# eeZee_medium_tiny.net
KiCad netlist of a schematic drawn in EAGLE
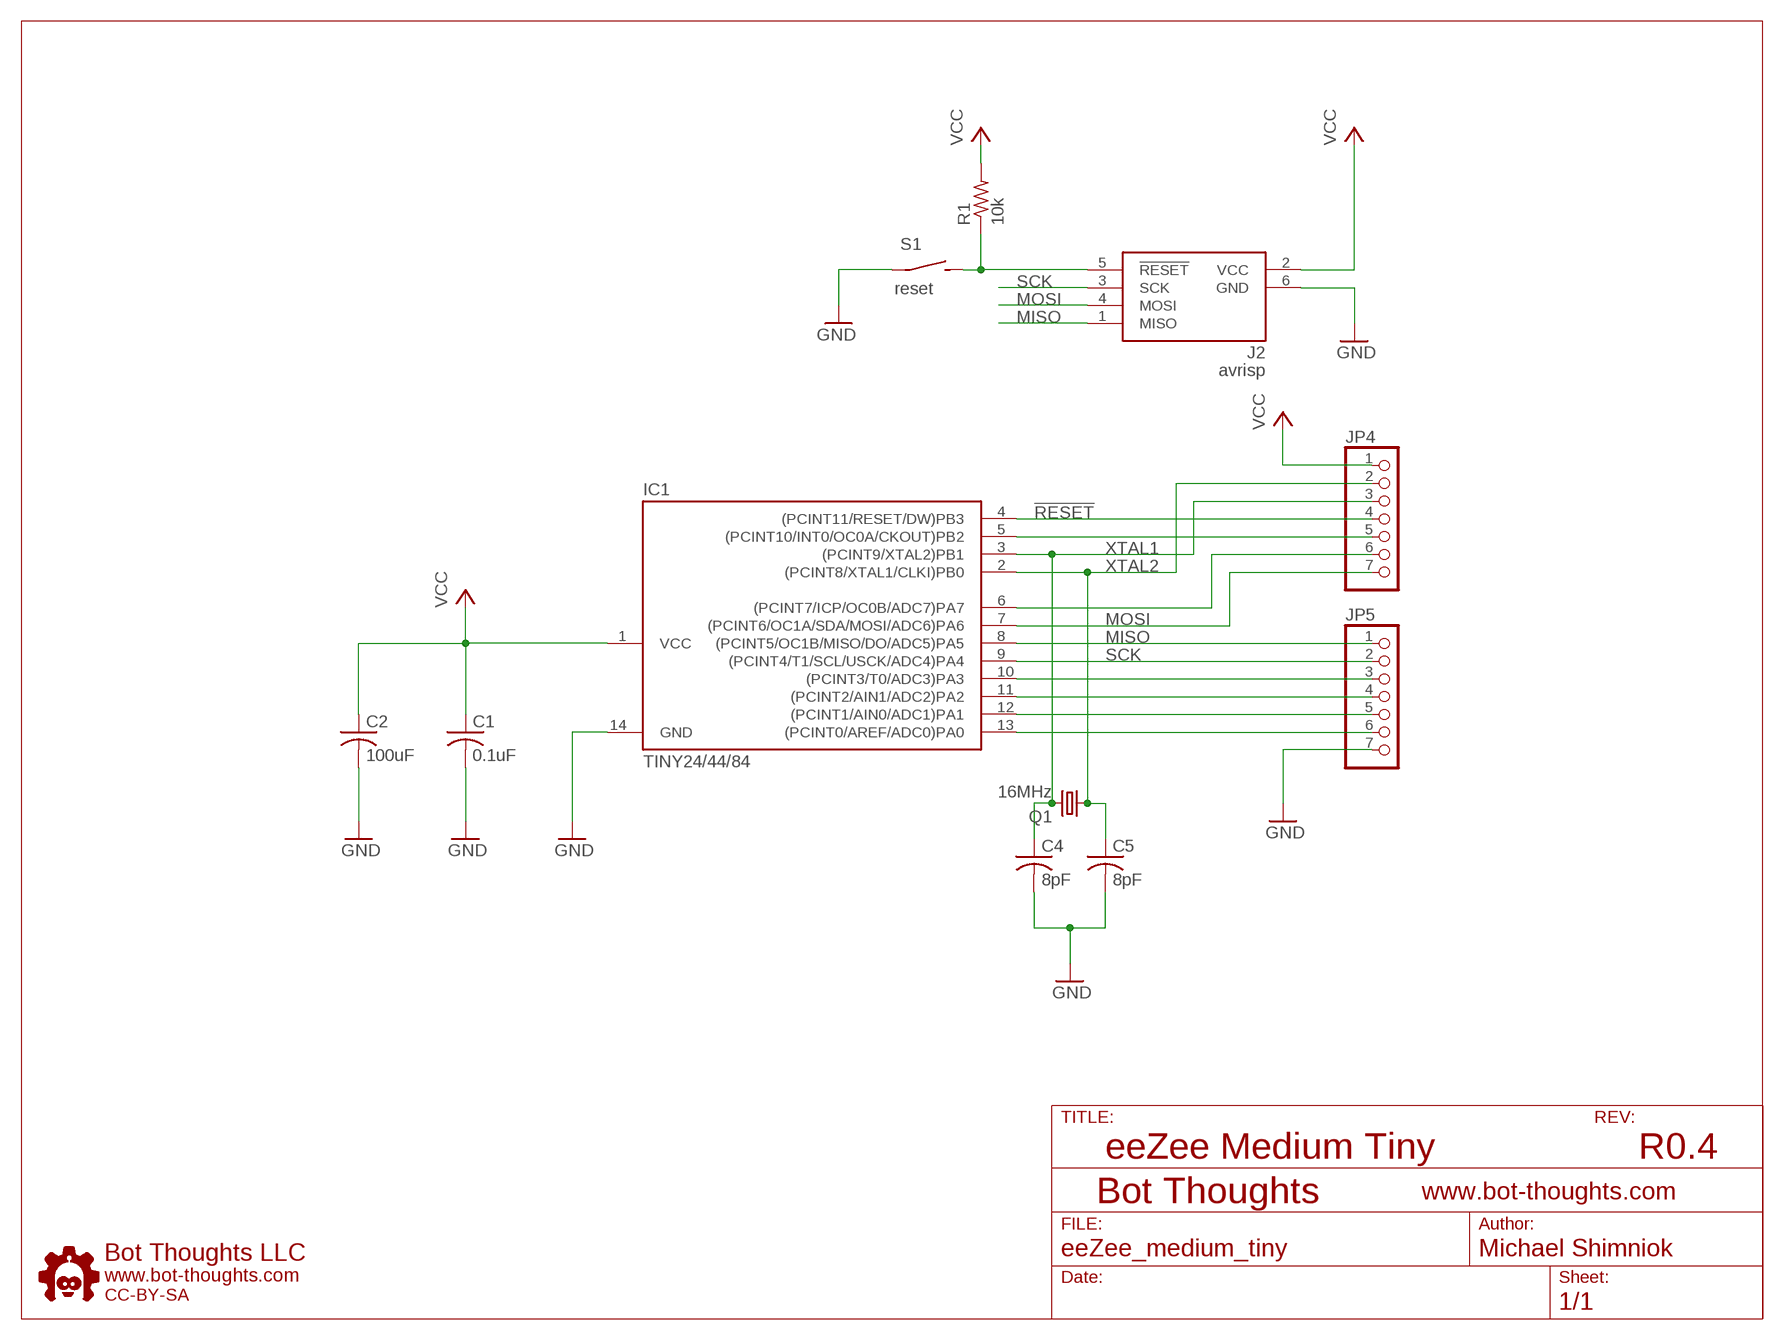
[diagram p0: schematic, sheet 1]

(export (version "E")
  (design (tool "Eeschema 10.0.6"))
  (components
    (comp (ref "C1")
      (value "0.1uF")
      (footprint "eagle-import:C0603")
      (fields (field (name "PARTNO") "0603YC104KAT2A"))
      (libsource (lib "eagle-import") (part "C-USC0603"))
    )
    (comp (ref "C2")
      (value "100uF")
      (footprint "eagle-import:C1206")
      (fields (field (name "PARTNO") "MCTT21X106M6R3CT"))
      (libsource (lib "eagle-import") (part "C-USC1206"))
    )
    (comp (ref "C4")
      (value "8pF")
      (footprint "eagle-import:C0603")
      (fields (field (name "PARTNO") "0603YC104KAT2A"))
      (libsource (lib "eagle-import") (part "C-USC0603"))
    )
    (comp (ref "C5")
      (value "8pF")
      (footprint "eagle-import:C0603")
      (fields (field (name "PARTNO") "0603YC104KAT2A"))
      (libsource (lib "eagle-import") (part "C-USC0603"))
    )
    (comp (ref "IC1")
      (value "TINY24/44/84")
      (footprint "eagle-import:DIL14")
      (libsource (lib "eagle-import") (part "TINY24/44/84-PU"))
    )
    (comp (ref "J2")
      (value "avrisp")
      (footprint "eagle-import:CON6P2R")
      (libsource (lib "eagle-import") (part "AVRISP6"))
    )
    (comp (ref "JP4")
      (value "PINHD-1X07_2.54-S")
      (footprint "eagle-import:1X07-S")
      (libsource (lib "eagle-import") (part "PINHD-1X07_2.54-S"))
    )
    (comp (ref "JP5")
      (value "PINHD-1X07_2.54-S")
      (footprint "eagle-import:1X07-S")
      (libsource (lib "eagle-import") (part "PINHD-1X07_2.54-S"))
    )
    (comp (ref "Q1")
      (value "16MHz")
      (footprint "eagle-import:NDK_2PAD_5X3")
      (libsource (lib "eagle-import") (part "CRYSTALNDK5X3"))
    )
    (comp (ref "R1")
      (value "10k")
      (footprint "eagle-import:R0603")
      (fields (field (name "PARTNO") "ERJ-3GEYJ103V"))
      (libsource (lib "eagle-import") (part "R-US_R0603"))
    )
    (comp (ref "S1")
      (value "reset")
      (footprint "eagle-import:6MMTACTILE_RECT")
      (libsource (lib "eagle-import") (part "SPST_TAC_RECT1"))
    )
    (comp (ref "U$1")
      (value "BTLOGO-LOGO-SM")
      (footprint "eagle-import:BTLOGOS")
      (libsource (lib "eagle-import") (part "BTLOGO-LOGO-SM"))
    )
  )
  (nets
    (net (code "1") (name "/MISO") (class "Default")
      (node (ref "IC1") (pin "8") (pinfunction "(PCINT5/OC1B/MISO/DO/ADC5)PA5_8") (pintype "bidirectional"))
      (node (ref "J2") (pin "1") (pinfunction "MISO_1") (pintype "input"))
      (node (ref "JP5") (pin "1") (pinfunction "1_1") (pintype "passive"))
    )
    (net (code "2") (name "/MOSI") (class "Default")
      (node (ref "IC1") (pin "7") (pinfunction "(PCINT6/OC1A/SDA/MOSI/ADC6)PA6_7") (pintype "bidirectional"))
      (node (ref "J2") (pin "4") (pinfunction "MOSI_4") (pintype "output"))
      (node (ref "JP4") (pin "7") (pinfunction "7_7") (pintype "passive"))
    )
    (net (code "3") (name "/SCK") (class "Default")
      (node (ref "IC1") (pin "9") (pinfunction "(PCINT4/T1/SCL/USCK/ADC4)PA4_9") (pintype "bidirectional"))
      (node (ref "J2") (pin "3") (pinfunction "SCK_3") (pintype "output"))
      (node (ref "JP5") (pin "2") (pinfunction "2_2") (pintype "passive"))
    )
    (net (code "4") (name "/XTAL1") (class "Default")
      (node (ref "C5") (pin "1") (pinfunction "1_1") (pintype "passive"))
      (node (ref "IC1") (pin "2") (pinfunction "(PCINT8/XTAL1/CLKI)PB0_2") (pintype "bidirectional"))
      (node (ref "JP4") (pin "2") (pinfunction "2_2") (pintype "passive"))
      (node (ref "Q1") (pin "P$1") (pinfunction "1_P$1") (pintype "passive"))
    )
    (net (code "5") (name "/XTAL2") (class "Default")
      (node (ref "C4") (pin "1") (pinfunction "1_1") (pintype "passive"))
      (node (ref "IC1") (pin "3") (pinfunction "(PCINT9/XTAL2)PB1_3") (pintype "bidirectional"))
      (node (ref "JP4") (pin "3") (pinfunction "3_3") (pintype "passive"))
      (node (ref "Q1") (pin "P$2") (pinfunction "2_P$2") (pintype "passive"))
    )
    (net (code "6") (name "/~{RESET}") (class "Default")
      (node (ref "IC1") (pin "4") (pinfunction "(PCINT11/RESET/DW)PB3_4") (pintype "bidirectional"))
      (node (ref "J2") (pin "5") (pinfunction "~{RESET}_5") (pintype "output"))
      (node (ref "JP4") (pin "4") (pinfunction "4_4") (pintype "passive"))
      (node (ref "R1") (pin "1") (pinfunction "1_1") (pintype "passive"))
      (node (ref "S1") (pin "P$2") (pinfunction "S_P$2") (pintype "passive"))
    )
    (net (code "7") (name "GND") (class "Default")
      (node (ref "C1") (pin "2") (pinfunction "2_2") (pintype "passive"))
      (node (ref "C2") (pin "2") (pinfunction "2_2") (pintype "passive"))
      (node (ref "C4") (pin "2") (pinfunction "2_2") (pintype "passive"))
      (node (ref "C5") (pin "2") (pinfunction "2_2") (pintype "passive"))
      (node (ref "IC1") (pin "14") (pinfunction "GND_14") (pintype "power_in"))
      (node (ref "J2") (pin "6") (pinfunction "GND_6") (pintype "power_in"))
      (node (ref "JP5") (pin "7") (pinfunction "7_7") (pintype "passive"))
      (node (ref "S1") (pin "P$1") (pinfunction "P_P$1") (pintype "passive"))
    )
    (net (code "8") (name "Net-(IC1-(PCINT0{slash}AREF{slash}ADC0)PA0)") (class "Default")
      (node (ref "IC1") (pin "13") (pinfunction "(PCINT0/AREF/ADC0)PA0_13") (pintype "bidirectional"))
      (node (ref "JP5") (pin "6") (pinfunction "6_6") (pintype "passive"))
    )
    (net (code "9") (name "Net-(IC1-(PCINT1{slash}AIN0{slash}ADC1)PA1)") (class "Default")
      (node (ref "IC1") (pin "12") (pinfunction "(PCINT1/AIN0/ADC1)PA1_12") (pintype "bidirectional"))
      (node (ref "JP5") (pin "5") (pinfunction "5_5") (pintype "passive"))
    )
    (net (code "10") (name "Net-(IC1-(PCINT2{slash}AIN1{slash}ADC2)PA2)") (class "Default")
      (node (ref "IC1") (pin "11") (pinfunction "(PCINT2/AIN1/ADC2)PA2_11") (pintype "bidirectional"))
      (node (ref "JP5") (pin "4") (pinfunction "4_4") (pintype "passive"))
    )
    (net (code "11") (name "Net-(IC1-(PCINT3{slash}T0{slash}ADC3)PA3)") (class "Default")
      (node (ref "IC1") (pin "10") (pinfunction "(PCINT3/T0/ADC3)PA3_10") (pintype "bidirectional"))
      (node (ref "JP5") (pin "3") (pinfunction "3_3") (pintype "passive"))
    )
    (net (code "12") (name "Net-(IC1-(PCINT7{slash}ICP{slash}OC0B{slash}ADC7)PA7)") (class "Default")
      (node (ref "IC1") (pin "6") (pinfunction "(PCINT7/ICP/OC0B/ADC7)PA7_6") (pintype "bidirectional"))
      (node (ref "JP4") (pin "6") (pinfunction "6_6") (pintype "passive"))
    )
    (net (code "13") (name "Net-(IC1-(PCINT10{slash}INT0{slash}OC0A{slash}CKOUT)PB2)") (class "Default")
      (node (ref "IC1") (pin "5") (pinfunction "(PCINT10/INT0/OC0A/CKOUT)PB2_5") (pintype "bidirectional"))
      (node (ref "JP4") (pin "5") (pinfunction "5_5") (pintype "passive"))
    )
    (net (code "14") (name "VCC") (class "Default")
      (node (ref "C1") (pin "1") (pinfunction "1_1") (pintype "passive"))
      (node (ref "C2") (pin "1") (pinfunction "1_1") (pintype "passive"))
      (node (ref "IC1") (pin "1") (pinfunction "VCC_1") (pintype "power_in"))
      (node (ref "J2") (pin "2") (pinfunction "VCC_2") (pintype "power_in"))
      (node (ref "JP4") (pin "1") (pinfunction "1_1") (pintype "passive"))
      (node (ref "R1") (pin "2") (pinfunction "2_2") (pintype "passive"))
    )
  )
)
